# IRInterface.net
KiCad netlist of a schematic drawn in EAGLE
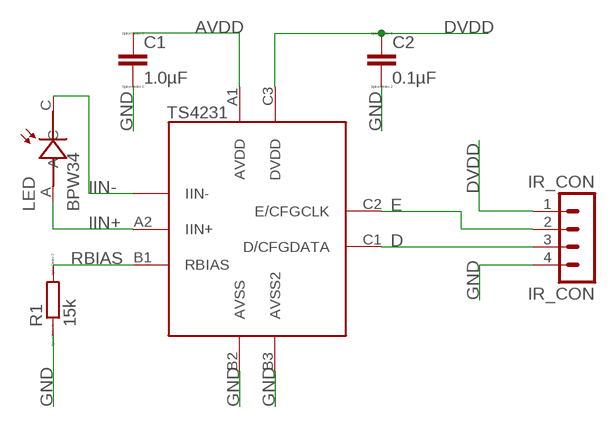
[diagram p0: schematic, sheet 1]

(export (version "E")
  (design (tool "Eeschema 10.0.6"))
  (components
    (comp (ref "C1")
      (value "1.0µF")
      (footprint "eagle-import:C0402")
      (libsource (lib "eagle-import") (part "CC0402"))
    )
    (comp (ref "C2")
      (value "0.1µF")
      (footprint "eagle-import:C0402")
      (libsource (lib "eagle-import") (part "CC0402"))
    )
    (comp (ref "IR_CON")
      (value "IR_CON")
      (footprint "eagle-import:MA04-1")
      (libsource (lib "eagle-import") (part "MA04-1"))
    )
    (comp (ref "LED")
      (value "BPW34")
      (footprint "eagle-import:PHODET_BPW34")
      (fields (field (name "MF") "Vishay"))
      (libsource (lib "eagle-import") (part "BPW34"))
    )
    (comp (ref "R1")
      (value "15k")
      (footprint "eagle-import:R0402")
      (libsource (lib "eagle-import") (part "RR0402"))
    )
    (comp (ref "TS4231")
      (value "TS4231SMD-9")
      (footprint "eagle-import:WLCSP-9")
      (libsource (lib "eagle-import") (part "TS4231SMD-9"))
    )
  )
  (nets
    (net (code "1") (name "/AVDD") (class "Default")
      (node (ref "C1") (pin "1") (pinfunction "1_1") (pintype "passive"))
      (node (ref "TS4231") (pin "A1") (pinfunction "AVDD_A1") (pintype "power_in"))
    )
    (net (code "2") (name "/D") (class "Default")
      (node (ref "IR_CON") (pin "3") (pinfunction "3_3") (pintype "passive"))
      (node (ref "TS4231") (pin "C1") (pinfunction "D/CFGDATA_C1") (pintype "bidirectional"))
    )
    (net (code "3") (name "/DVDD") (class "Default")
      (node (ref "C2") (pin "1") (pinfunction "1_1") (pintype "passive"))
      (node (ref "IR_CON") (pin "1") (pinfunction "1_1") (pintype "passive"))
      (node (ref "TS4231") (pin "C3") (pinfunction "DVDD_C3") (pintype "power_in"))
    )
    (net (code "4") (name "/E") (class "Default")
      (node (ref "IR_CON") (pin "2") (pinfunction "2_2") (pintype "passive"))
      (node (ref "TS4231") (pin "C2") (pinfunction "E/CFGCLK_C2") (pintype "bidirectional"))
    )
    (net (code "5") (name "/GND") (class "Default")
      (node (ref "C1") (pin "2") (pinfunction "2_2") (pintype "passive"))
      (node (ref "C2") (pin "2") (pinfunction "2_2") (pintype "passive"))
      (node (ref "IR_CON") (pin "4") (pinfunction "4_4") (pintype "passive"))
      (node (ref "R1") (pin "1") (pinfunction "1_1") (pintype "passive"))
      (node (ref "TS4231") (pin "B2") (pinfunction "AVSS_B2") (pintype "power_in"))
      (node (ref "TS4231") (pin "B3") (pinfunction "AVSS2_B3") (pintype "power_in"))
    )
    (net (code "6") (name "/IIN+") (class "Default")
      (node (ref "LED") (pin "A") (pinfunction "A_A") (pintype "passive"))
      (node (ref "TS4231") (pin "A2") (pinfunction "IIN+_A2") (pintype "input"))
    )
    (net (code "7") (name "/IIN-") (class "Default")
      (node (ref "LED") (pin "C") (pinfunction "C_C") (pintype "passive"))
      (node (ref "TS4231") (pin "A3") (pinfunction "IIN-_A3") (pintype "input"))
    )
    (net (code "8") (name "/RBIAS") (class "Default")
      (node (ref "R1") (pin "2") (pinfunction "2_2") (pintype "passive"))
      (node (ref "TS4231") (pin "B1") (pinfunction "RBIAS_B1") (pintype "input"))
    )
  )
)
